# rj45_bnc.net
KiCad netlist of a schematic drawn in Altium Designer
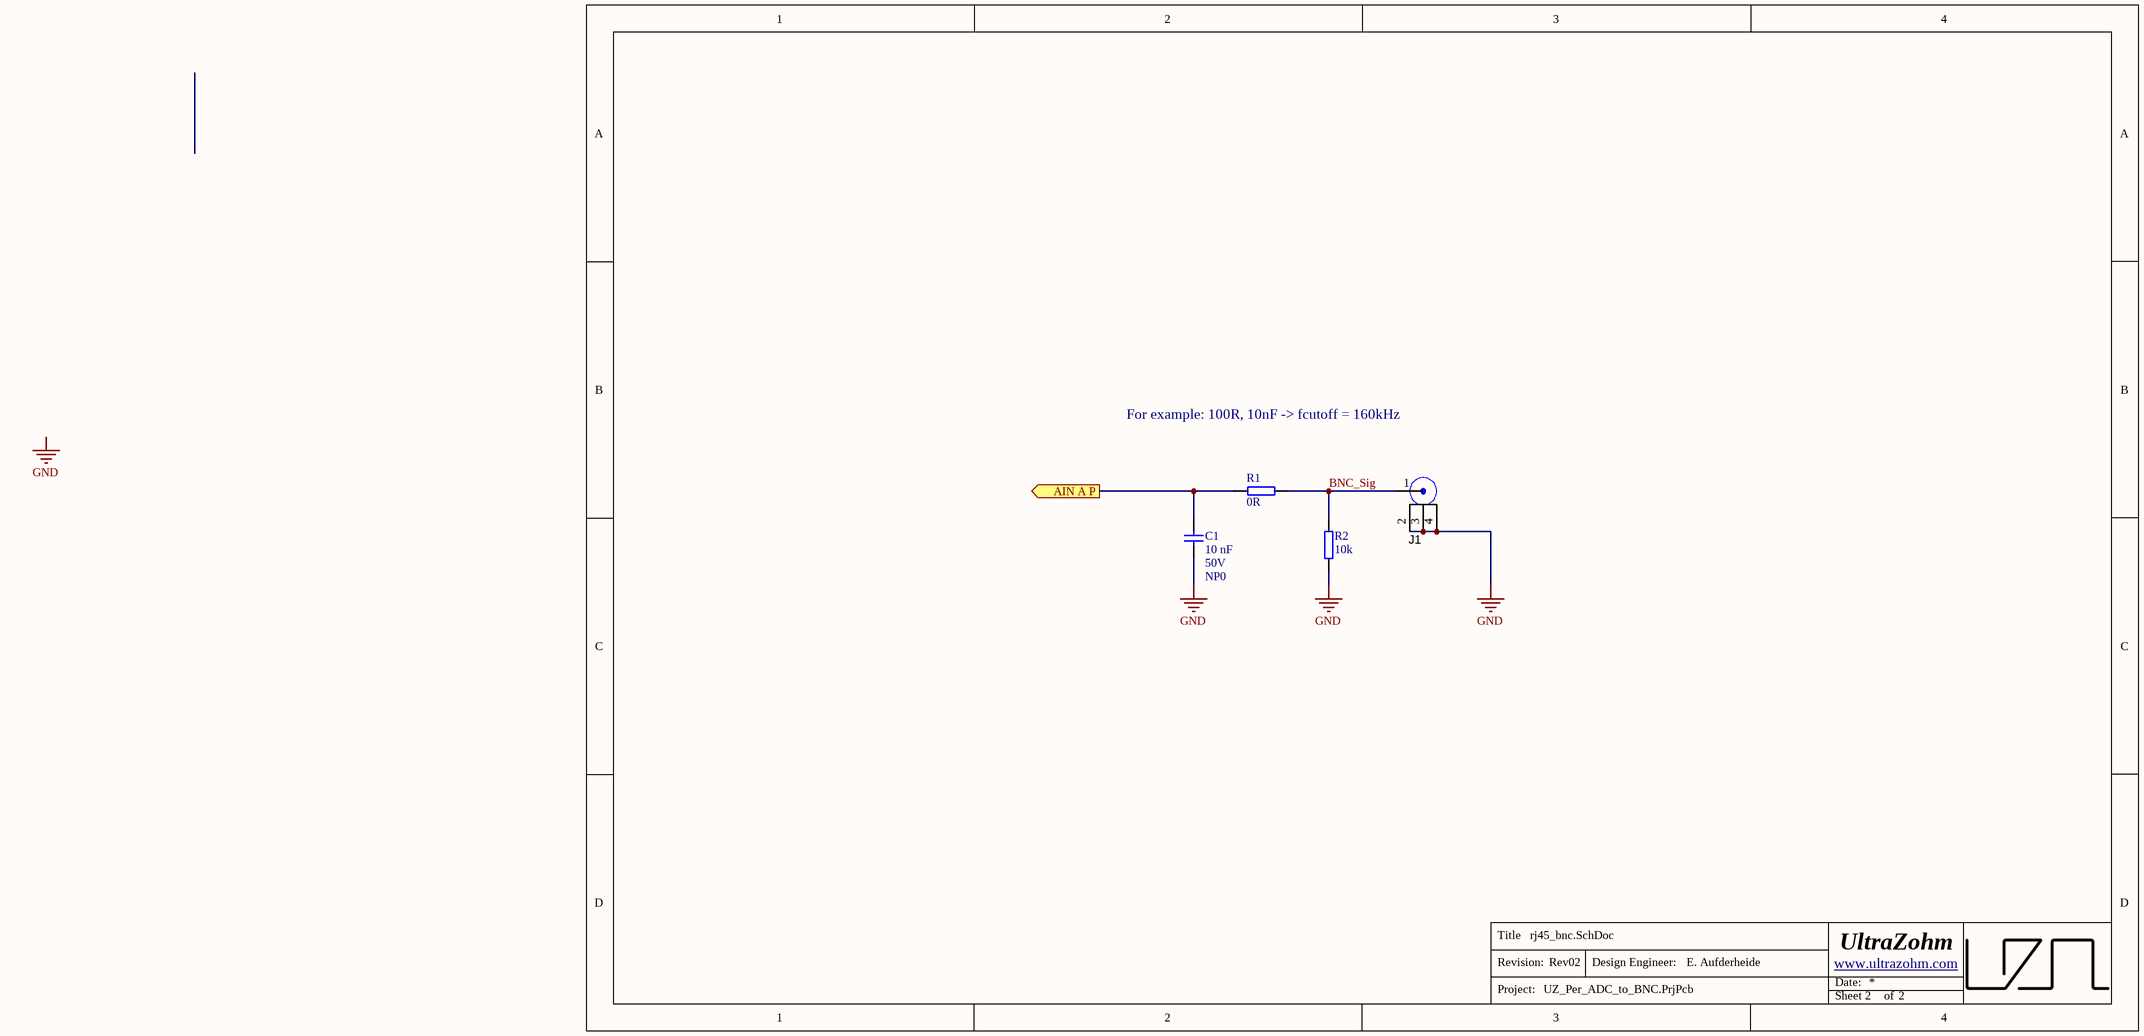
[diagram p0: rj45_bnc.SchDoc]

(export (version "E")
  (design (tool "Eeschema 10.0.6"))
  (components
    (comp (ref "C1")
      (value "10 nF")
      (footprint "C_0603_TE")
      (description "Generic capacitor")
      (fields
        (field (name "MANUFACTURER PART NUMBER") "UZgen_C_0603_10nF_50V_NP0")
        (field (name "MANUFACTURER") "UZgen")
        (field (name "VOLTAGE") "50V")
        (field (name "TECHNOLOGY") "NP0")
        (field (name "CREATED FROM") "UZgenTool")
      )
      (libsource (lib "user") (part "CAP-NP"))
    )
    (comp (ref "J1")
      (value "~")
      (footprint "Right Angle BNC")
      (description "RF Connectors / Coaxial Connectors 50 Ohm BNC Jack and Plug / right-angle")
      (fields
        (field (name "MANUFACTURER") "TE Connectivity")
        (field (name "PARTNUMBER") "Used in BOM report")
        (field (name "SYMBOLCREATOR") "Use LDAP id")
        (field (name "CREATED FROM") "EAufderheide")
      )
      (libsource (lib "user") (part "BNC"))
    )
    (comp (ref "R1")
      (value "0R")
      (footprint "R_0603_TE")
      (description "Generic resistor")
      (fields
        (field (name "MANUFACTURER PART NUMBER") "UZgen_R_0603_0R")
        (field (name "MANUFACTURER") "UZgen")
        (field (name "CREATED FROM") "UZgenTool")
      )
      (libsource (lib "user") (part "RES"))
    )
    (comp (ref "R2")
      (value "10k")
      (footprint "R_0603_TE")
      (description "Generic resistor")
      (fields
        (field (name "MANUFACTURER PART NUMBER") "UZgen_R_0603_10k")
        (field (name "MANUFACTURER") "UZgen")
        (field (name "CREATED FROM") "AGeiger")
      )
      (libsource (lib "user") (part "RES"))
    )
  )
  (nets
    (net (code "1") (name "/AIN A P") (class "Default")
      (node (ref "C1") (pin "1") (pinfunction "1_1") (pintype "passive"))
      (node (ref "R1") (pin "2") (pinfunction "2_2") (pintype "passive"))
    )
    (net (code "2") (name "/BNC_Sig") (class "Default")
      (node (ref "J1") (pin "1") (pinfunction "1_1") (pintype "passive"))
      (node (ref "R1") (pin "1") (pinfunction "1_1") (pintype "passive"))
      (node (ref "R2") (pin "2") (pinfunction "2_2") (pintype "passive"))
    )
    (net (code "3") (name "GND") (class "Default")
      (node (ref "C1") (pin "2") (pinfunction "2_2") (pintype "passive"))
      (node (ref "J1") (pin "2") (pinfunction "2_2") (pintype "passive"))
      (node (ref "J1") (pin "3") (pinfunction "3_3") (pintype "passive"))
      (node (ref "J1") (pin "4") (pinfunction "4_4") (pintype "passive"))
      (node (ref "R2") (pin "1") (pinfunction "1_1") (pintype "passive"))
    )
  )
)
